# DIOT_signal_routing.net
KiCad netlist of a schematic drawn in Altium Designer
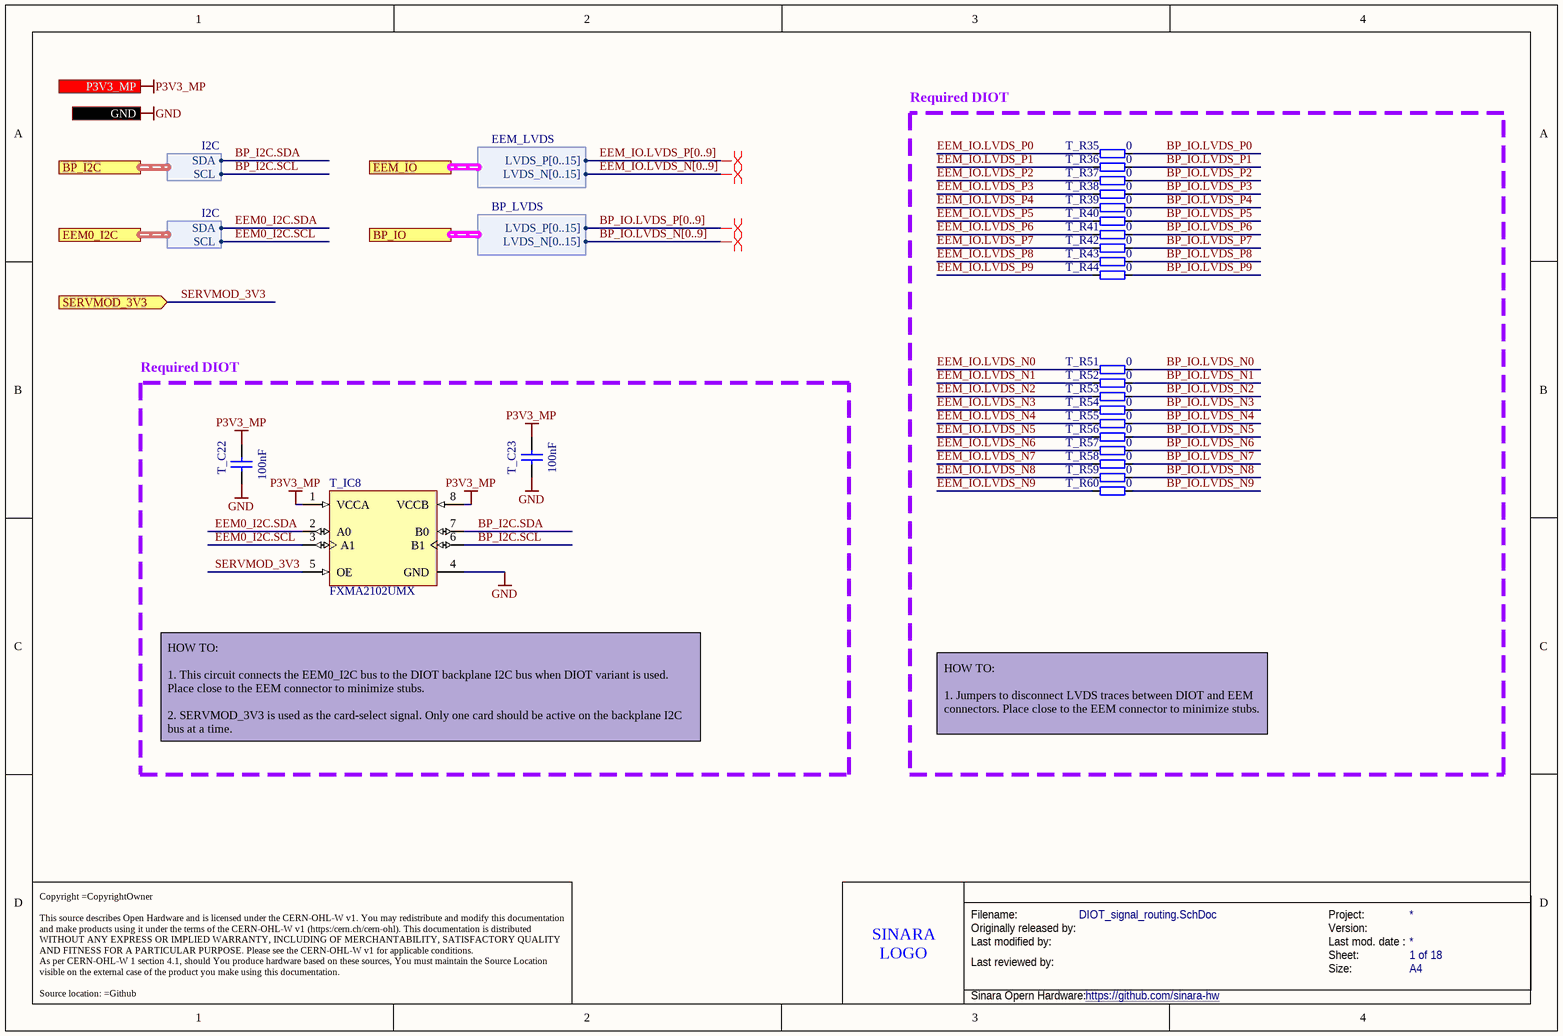
[diagram p0: DIOT_signal_routing.SchDoc]

(export (version "E")
  (design (tool "Eeschema 10.0.6"))
  (components
    (comp (ref "T_C22")
      (value "100nF")
      (footprint "CAPC1005X55N")
      (description "Non-polarised capacitor")
      (fields
        (field (name "PART NUMBER") "CC0402_100NF_16V_10%_X5R")
        (field (name "VOLTAGE") "16V")
        (field (name "AUTHOR") "CERN DEM JLC")
      )
      (libsource (lib "Capacitors") (part "Capacitor - non polarized"))
    )
    (comp (ref "T_C23")
      (value "100nF")
      (footprint "CAPC1005X55N")
      (description "Non-polarised capacitor")
      (fields
        (field (name "PART NUMBER") "CC0402_100NF_16V_10%_X5R")
        (field (name "VOLTAGE") "16V")
        (field (name "AUTHOR") "CERN DEM JLC")
      )
      (libsource (lib "Capacitors") (part "Capacitor - non polarized"))
    )
    (comp (ref "T_IC8")
      (value "FXMA2102UMX")
      (footprint "FXMA2102UMX")
      (description "Dual Supply 2-Bit Voltage Translator/Buffer/Repeater Isolator for I2C Applications")
      (fields (field (name "MANUFACTURER") "Onsemi"))
      (libsource (lib "TechnoSystem Workspace") (part "FXMA2102UMX"))
    )
    (comp (ref "T_R35")
      (value "0")
      (footprint "RESC1005X40N")
      (description "Resistor")
      (fields
        (field (name "PART NUMBER") "R0402_0R_JUMPER")
        (field (name "MANUFACTURER") "GENERIC")
        (field (name "AUTHOR") "CERN DEM JLC")
      )
      (libsource (lib "Resistors") (part "Resistor"))
    )
    (comp (ref "T_R36")
      (value "0")
      (footprint "RESC1005X40N")
      (description "Resistor")
      (fields
        (field (name "PART NUMBER") "R0402_0R_JUMPER")
        (field (name "MANUFACTURER") "GENERIC")
        (field (name "AUTHOR") "CERN DEM JLC")
      )
      (libsource (lib "Resistors") (part "Resistor"))
    )
    (comp (ref "T_R37")
      (value "0")
      (footprint "RESC1005X40N")
      (description "Resistor")
      (fields
        (field (name "PART NUMBER") "R0402_0R_JUMPER")
        (field (name "MANUFACTURER") "GENERIC")
        (field (name "AUTHOR") "CERN DEM JLC")
      )
      (libsource (lib "Resistors") (part "Resistor"))
    )
    (comp (ref "T_R38")
      (value "0")
      (footprint "RESC1005X40N")
      (description "Resistor")
      (fields
        (field (name "PART NUMBER") "R0402_0R_JUMPER")
        (field (name "MANUFACTURER") "GENERIC")
        (field (name "AUTHOR") "CERN DEM JLC")
      )
      (libsource (lib "Resistors") (part "Resistor"))
    )
    (comp (ref "T_R39")
      (value "0")
      (footprint "RESC1005X40N")
      (description "Resistor")
      (fields
        (field (name "PART NUMBER") "R0402_0R_JUMPER")
        (field (name "MANUFACTURER") "GENERIC")
        (field (name "AUTHOR") "CERN DEM JLC")
      )
      (libsource (lib "Resistors") (part "Resistor"))
    )
    (comp (ref "T_R40")
      (value "0")
      (footprint "RESC1005X40N")
      (description "Resistor")
      (fields
        (field (name "PART NUMBER") "R0402_0R_JUMPER")
        (field (name "MANUFACTURER") "GENERIC")
        (field (name "AUTHOR") "CERN DEM JLC")
      )
      (libsource (lib "Resistors") (part "Resistor"))
    )
    (comp (ref "T_R41")
      (value "0")
      (footprint "RESC1005X40N")
      (description "Resistor")
      (fields
        (field (name "PART NUMBER") "R0402_0R_JUMPER")
        (field (name "MANUFACTURER") "GENERIC")
        (field (name "AUTHOR") "CERN DEM JLC")
      )
      (libsource (lib "Resistors") (part "Resistor"))
    )
    (comp (ref "T_R42")
      (value "0")
      (footprint "RESC1005X40N")
      (description "Resistor")
      (fields
        (field (name "PART NUMBER") "R0402_0R_JUMPER")
        (field (name "MANUFACTURER") "GENERIC")
        (field (name "AUTHOR") "CERN DEM JLC")
      )
      (libsource (lib "Resistors") (part "Resistor"))
    )
    (comp (ref "T_R43")
      (value "0")
      (footprint "RESC1005X40N")
      (description "Resistor")
      (fields
        (field (name "PART NUMBER") "R0402_0R_JUMPER")
        (field (name "MANUFACTURER") "GENERIC")
        (field (name "AUTHOR") "CERN DEM JLC")
      )
      (libsource (lib "Resistors") (part "Resistor"))
    )
    (comp (ref "T_R44")
      (value "0")
      (footprint "RESC1005X40N")
      (description "Resistor")
      (fields
        (field (name "PART NUMBER") "R0402_0R_JUMPER")
        (field (name "MANUFACTURER") "GENERIC")
        (field (name "AUTHOR") "CERN DEM JLC")
      )
      (libsource (lib "Resistors") (part "Resistor"))
    )
    (comp (ref "T_R51")
      (value "0")
      (footprint "RESC1005X40N")
      (description "Resistor")
      (fields
        (field (name "PART NUMBER") "R0402_0R_JUMPER")
        (field (name "MANUFACTURER") "GENERIC")
        (field (name "AUTHOR") "CERN DEM JLC")
      )
      (libsource (lib "Resistors") (part "Resistor"))
    )
    (comp (ref "T_R52")
      (value "0")
      (footprint "RESC1005X40N")
      (description "Resistor")
      (fields
        (field (name "PART NUMBER") "R0402_0R_JUMPER")
        (field (name "MANUFACTURER") "GENERIC")
        (field (name "AUTHOR") "CERN DEM JLC")
      )
      (libsource (lib "Resistors") (part "Resistor"))
    )
    (comp (ref "T_R53")
      (value "0")
      (footprint "RESC1005X40N")
      (description "Resistor")
      (fields
        (field (name "PART NUMBER") "R0402_0R_JUMPER")
        (field (name "MANUFACTURER") "GENERIC")
        (field (name "AUTHOR") "CERN DEM JLC")
      )
      (libsource (lib "Resistors") (part "Resistor"))
    )
    (comp (ref "T_R54")
      (value "0")
      (footprint "RESC1005X40N")
      (description "Resistor")
      (fields
        (field (name "PART NUMBER") "R0402_0R_JUMPER")
        (field (name "MANUFACTURER") "GENERIC")
        (field (name "AUTHOR") "CERN DEM JLC")
      )
      (libsource (lib "Resistors") (part "Resistor"))
    )
    (comp (ref "T_R55")
      (value "0")
      (footprint "RESC1005X40N")
      (description "Resistor")
      (fields
        (field (name "PART NUMBER") "R0402_0R_JUMPER")
        (field (name "MANUFACTURER") "GENERIC")
        (field (name "AUTHOR") "CERN DEM JLC")
      )
      (libsource (lib "Resistors") (part "Resistor"))
    )
    (comp (ref "T_R56")
      (value "0")
      (footprint "RESC1005X40N")
      (description "Resistor")
      (fields
        (field (name "PART NUMBER") "R0402_0R_JUMPER")
        (field (name "MANUFACTURER") "GENERIC")
        (field (name "AUTHOR") "CERN DEM JLC")
      )
      (libsource (lib "Resistors") (part "Resistor"))
    )
    (comp (ref "T_R57")
      (value "0")
      (footprint "RESC1005X40N")
      (description "Resistor")
      (fields
        (field (name "PART NUMBER") "R0402_0R_JUMPER")
        (field (name "MANUFACTURER") "GENERIC")
        (field (name "AUTHOR") "CERN DEM JLC")
      )
      (libsource (lib "Resistors") (part "Resistor"))
    )
    (comp (ref "T_R58")
      (value "0")
      (footprint "RESC1005X40N")
      (description "Resistor")
      (fields
        (field (name "PART NUMBER") "R0402_0R_JUMPER")
        (field (name "MANUFACTURER") "GENERIC")
        (field (name "AUTHOR") "CERN DEM JLC")
      )
      (libsource (lib "Resistors") (part "Resistor"))
    )
    (comp (ref "T_R59")
      (value "0")
      (footprint "RESC1005X40N")
      (description "Resistor")
      (fields
        (field (name "PART NUMBER") "R0402_0R_JUMPER")
        (field (name "MANUFACTURER") "GENERIC")
        (field (name "AUTHOR") "CERN DEM JLC")
      )
      (libsource (lib "Resistors") (part "Resistor"))
    )
    (comp (ref "T_R60")
      (value "0")
      (footprint "RESC1005X40N")
      (description "Resistor")
      (fields
        (field (name "PART NUMBER") "R0402_0R_JUMPER")
        (field (name "MANUFACTURER") "GENERIC")
        (field (name "AUTHOR") "CERN DEM JLC")
      )
      (libsource (lib "Resistors") (part "Resistor"))
    )
  )
  (nets
    (net (code "4") (name "/BP_I2C.SCL") (class "Default")
      (node (ref "T_IC8") (pin "6") (pinfunction "B1_6") (pintype "bidirectional"))
    )
    (net (code "5") (name "/BP_I2C.SDA") (class "Default")
      (node (ref "T_IC8") (pin "7") (pinfunction "B0_7") (pintype "bidirectional"))
    )
    (net (code "6") (name "/BP_IO.LVDS_N0") (class "Default")
      (node (ref "T_R51") (pin "1") (pinfunction "1_1") (pintype "passive"))
    )
    (net (code "7") (name "/BP_IO.LVDS_N1") (class "Default")
      (node (ref "T_R52") (pin "1") (pinfunction "1_1") (pintype "passive"))
    )
    (net (code "8") (name "/BP_IO.LVDS_N2") (class "Default")
      (node (ref "T_R53") (pin "1") (pinfunction "1_1") (pintype "passive"))
    )
    (net (code "9") (name "/BP_IO.LVDS_N3") (class "Default")
      (node (ref "T_R54") (pin "1") (pinfunction "1_1") (pintype "passive"))
    )
    (net (code "10") (name "/BP_IO.LVDS_N4") (class "Default")
      (node (ref "T_R55") (pin "1") (pinfunction "1_1") (pintype "passive"))
    )
    (net (code "11") (name "/BP_IO.LVDS_N5") (class "Default")
      (node (ref "T_R56") (pin "1") (pinfunction "1_1") (pintype "passive"))
    )
    (net (code "12") (name "/BP_IO.LVDS_N6") (class "Default")
      (node (ref "T_R57") (pin "1") (pinfunction "1_1") (pintype "passive"))
    )
    (net (code "13") (name "/BP_IO.LVDS_N7") (class "Default")
      (node (ref "T_R58") (pin "1") (pinfunction "1_1") (pintype "passive"))
    )
    (net (code "14") (name "/BP_IO.LVDS_N8") (class "Default")
      (node (ref "T_R59") (pin "1") (pinfunction "1_1") (pintype "passive"))
    )
    (net (code "15") (name "/BP_IO.LVDS_N9") (class "Default")
      (node (ref "T_R60") (pin "1") (pinfunction "1_1") (pintype "passive"))
    )
    (net (code "16") (name "/BP_IO.LVDS_P0") (class "Default")
      (node (ref "T_R35") (pin "1") (pinfunction "1_1") (pintype "passive"))
    )
    (net (code "17") (name "/BP_IO.LVDS_P1") (class "Default")
      (node (ref "T_R36") (pin "1") (pinfunction "1_1") (pintype "passive"))
    )
    (net (code "18") (name "/BP_IO.LVDS_P2") (class "Default")
      (node (ref "T_R37") (pin "1") (pinfunction "1_1") (pintype "passive"))
    )
    (net (code "19") (name "/BP_IO.LVDS_P3") (class "Default")
      (node (ref "T_R38") (pin "1") (pinfunction "1_1") (pintype "passive"))
    )
    (net (code "20") (name "/BP_IO.LVDS_P4") (class "Default")
      (node (ref "T_R39") (pin "1") (pinfunction "1_1") (pintype "passive"))
    )
    (net (code "21") (name "/BP_IO.LVDS_P5") (class "Default")
      (node (ref "T_R40") (pin "1") (pinfunction "1_1") (pintype "passive"))
    )
    (net (code "22") (name "/BP_IO.LVDS_P6") (class "Default")
      (node (ref "T_R41") (pin "1") (pinfunction "1_1") (pintype "passive"))
    )
    (net (code "23") (name "/BP_IO.LVDS_P7") (class "Default")
      (node (ref "T_R42") (pin "1") (pinfunction "1_1") (pintype "passive"))
    )
    (net (code "24") (name "/BP_IO.LVDS_P8") (class "Default")
      (node (ref "T_R43") (pin "1") (pinfunction "1_1") (pintype "passive"))
    )
    (net (code "25") (name "/BP_IO.LVDS_P9") (class "Default")
      (node (ref "T_R44") (pin "1") (pinfunction "1_1") (pintype "passive"))
    )
    (net (code "28") (name "/EEM0_I2C.SCL") (class "Default")
      (node (ref "T_IC8") (pin "3") (pinfunction "A1_3") (pintype "bidirectional"))
    )
    (net (code "29") (name "/EEM0_I2C.SDA") (class "Default")
      (node (ref "T_IC8") (pin "2") (pinfunction "A0_2") (pintype "bidirectional"))
    )
    (net (code "30") (name "/EEM_IO.LVDS_N0") (class "Default")
      (node (ref "T_R51") (pin "2") (pinfunction "2_2") (pintype "passive"))
    )
    (net (code "31") (name "/EEM_IO.LVDS_N1") (class "Default")
      (node (ref "T_R52") (pin "2") (pinfunction "2_2") (pintype "passive"))
    )
    (net (code "32") (name "/EEM_IO.LVDS_N2") (class "Default")
      (node (ref "T_R53") (pin "2") (pinfunction "2_2") (pintype "passive"))
    )
    (net (code "33") (name "/EEM_IO.LVDS_N3") (class "Default")
      (node (ref "T_R54") (pin "2") (pinfunction "2_2") (pintype "passive"))
    )
    (net (code "34") (name "/EEM_IO.LVDS_N4") (class "Default")
      (node (ref "T_R55") (pin "2") (pinfunction "2_2") (pintype "passive"))
    )
    (net (code "35") (name "/EEM_IO.LVDS_N5") (class "Default")
      (node (ref "T_R56") (pin "2") (pinfunction "2_2") (pintype "passive"))
    )
    (net (code "36") (name "/EEM_IO.LVDS_N6") (class "Default")
      (node (ref "T_R57") (pin "2") (pinfunction "2_2") (pintype "passive"))
    )
    (net (code "37") (name "/EEM_IO.LVDS_N7") (class "Default")
      (node (ref "T_R58") (pin "2") (pinfunction "2_2") (pintype "passive"))
    )
    (net (code "38") (name "/EEM_IO.LVDS_N8") (class "Default")
      (node (ref "T_R59") (pin "2") (pinfunction "2_2") (pintype "passive"))
    )
    (net (code "39") (name "/EEM_IO.LVDS_N9") (class "Default")
      (node (ref "T_R60") (pin "2") (pinfunction "2_2") (pintype "passive"))
    )
    (net (code "40") (name "/EEM_IO.LVDS_P0") (class "Default")
      (node (ref "T_R35") (pin "2") (pinfunction "2_2") (pintype "passive"))
    )
    (net (code "41") (name "/EEM_IO.LVDS_P1") (class "Default")
      (node (ref "T_R36") (pin "2") (pinfunction "2_2") (pintype "passive"))
    )
    (net (code "42") (name "/EEM_IO.LVDS_P2") (class "Default")
      (node (ref "T_R37") (pin "2") (pinfunction "2_2") (pintype "passive"))
    )
    (net (code "43") (name "/EEM_IO.LVDS_P3") (class "Default")
      (node (ref "T_R38") (pin "2") (pinfunction "2_2") (pintype "passive"))
    )
    (net (code "44") (name "/EEM_IO.LVDS_P4") (class "Default")
      (node (ref "T_R39") (pin "2") (pinfunction "2_2") (pintype "passive"))
    )
    (net (code "45") (name "/EEM_IO.LVDS_P5") (class "Default")
      (node (ref "T_R40") (pin "2") (pinfunction "2_2") (pintype "passive"))
    )
    (net (code "46") (name "/EEM_IO.LVDS_P6") (class "Default")
      (node (ref "T_R41") (pin "2") (pinfunction "2_2") (pintype "passive"))
    )
    (net (code "47") (name "/EEM_IO.LVDS_P7") (class "Default")
      (node (ref "T_R42") (pin "2") (pinfunction "2_2") (pintype "passive"))
    )
    (net (code "48") (name "/EEM_IO.LVDS_P8") (class "Default")
      (node (ref "T_R43") (pin "2") (pinfunction "2_2") (pintype "passive"))
    )
    (net (code "49") (name "/EEM_IO.LVDS_P9") (class "Default")
      (node (ref "T_R44") (pin "2") (pinfunction "2_2") (pintype "passive"))
    )
    (net (code "52") (name "/SERVMOD_3V3") (class "Default")
      (node (ref "T_IC8") (pin "5") (pinfunction "OE_5") (pintype "input"))
    )
    (net (code "54") (name "GND") (class "Default")
      (node (ref "T_C22") (pin "1") (pinfunction "1_1") (pintype "passive"))
      (node (ref "T_C23") (pin "1") (pinfunction "1_1") (pintype "passive"))
      (node (ref "T_IC8") (pin "4") (pinfunction "GND_4") (pintype "power_in"))
    )
    (net (code "55") (name "P3V3_MP") (class "Default")
      (node (ref "T_C22") (pin "2") (pinfunction "2_2") (pintype "passive"))
      (node (ref "T_C23") (pin "2") (pinfunction "2_2") (pintype "passive"))
      (node (ref "T_IC8") (pin "1") (pinfunction "VCCA_1") (pintype "input"))
      (node (ref "T_IC8") (pin "8") (pinfunction "VCCB_8") (pintype "input"))
    )
  )
)
